# TBA820-Amplifier.net
KiCad netlist of a schematic drawn in EAGLE
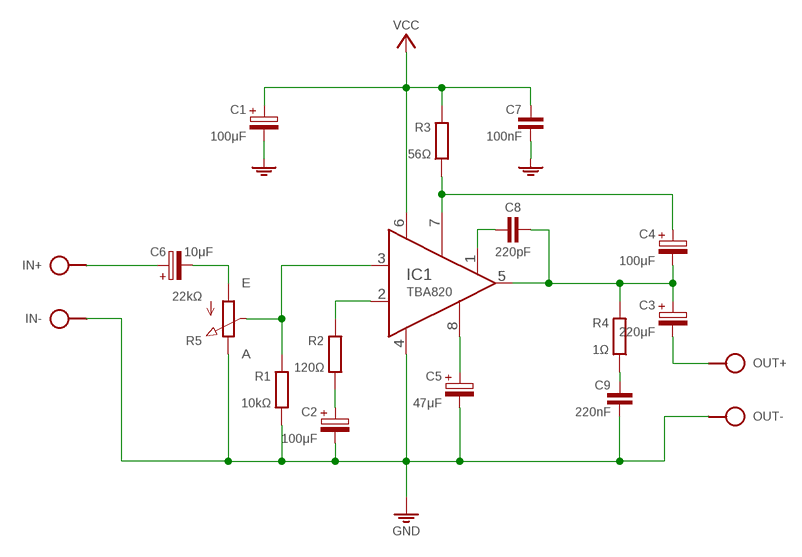
[diagram p0: schematic, sheet 1]

(export (version "E")
  (design (tool "Eeschema 10.0.6"))
  (components
    (comp (ref "C1")
      (value "100μF")
      (footprint "eagle-import:E2.5-4_V")
      (libsource (lib "eagle-import") (part "CPOLE2,5-4/V"))
    )
    (comp (ref "C2")
      (value "100μF")
      (footprint "eagle-import:E2.5-4_V")
      (libsource (lib "eagle-import") (part "CPOLE2,5-4/V"))
    )
    (comp (ref "C3")
      (value "220μF")
      (footprint "eagle-import:E2,5-5")
      (libsource (lib "eagle-import") (part "CPOLE2.5-5"))
    )
    (comp (ref "C4")
      (value "100μF")
      (footprint "eagle-import:E2.5-4_V")
      (libsource (lib "eagle-import") (part "CPOLE2,5-4/V"))
    )
    (comp (ref "C5")
      (value "47μF")
      (footprint "eagle-import:E2,5-3")
      (libsource (lib "eagle-import") (part "CPOLE2,5-3"))
    )
    (comp (ref "C6")
      (value "10μF")
      (footprint "eagle-import:E2,5-3")
      (libsource (lib "eagle-import") (part "CPOL-HE2,5-3"))
    )
    (comp (ref "C7")
      (value "100nF")
      (footprint "eagle-import:C025-024X044")
      (libsource (lib "eagle-import") (part "C025-024X044"))
    )
    (comp (ref "C8")
      (value "220pF")
      (footprint "eagle-import:C075-020X044")
      (libsource (lib "eagle-import") (part "C-H075-020X044"))
    )
    (comp (ref "C9")
      (value "220nF")
      (footprint "eagle-import:C075-020X044")
      (libsource (lib "eagle-import") (part "C075-020X044"))
    )
    (comp (ref "IC1")
      (value "TBA820")
      (footprint "eagle-import:DIL08")
      (libsource (lib "eagle-import") (part "TBA820"))
    )
    (comp (ref "IN")
      (value "SPAD+--+")
      (footprint "eagle-import:SPAD-+")
      (libsource (lib "eagle-import") (part "SPAD+--+"))
    )
    (comp (ref "OUT")
      (value "SPAD+-+-")
      (footprint "eagle-import:SPAD+-")
      (libsource (lib "eagle-import") (part "SPAD+-+-"))
    )
    (comp (ref "R1")
      (value "10kΩ")
      (footprint "eagle-import:0204_10-V")
      (libsource (lib "eagle-import") (part "R0204/10-V"))
    )
    (comp (ref "R2")
      (value "120Ω")
      (footprint "eagle-import:0202_2V")
      (libsource (lib "eagle-import") (part "R0202/2V"))
    )
    (comp (ref "R3")
      (value "56Ω")
      (footprint "eagle-import:0204_10-V")
      (libsource (lib "eagle-import") (part "R0204/10-V"))
    )
    (comp (ref "R4")
      (value "1Ω")
      (footprint "eagle-import:0204_10-V")
      (libsource (lib "eagle-import") (part "R0204/10-V"))
    )
    (comp (ref "R5")
      (value "22kΩ")
      (footprint "eagle-import:CONN-3P")
      (libsource (lib "eagle-import") (part "POT-3P"))
    )
    (comp (ref "S4")
      (value "VCC_GNDPWR-L")
      (footprint "eagle-import:PWR-L")
      (libsource (lib "eagle-import") (part "VCC_GNDPWR-L"))
    )
  )
  (nets
    (net (code "1") (name "GND") (class "Default")
      (node (ref "C1") (pin "-") (pinfunction "-_-") (pintype "passive"))
      (node (ref "C2") (pin "-") (pinfunction "-_-") (pintype "passive"))
      (node (ref "C5") (pin "-") (pinfunction "-_-") (pintype "passive"))
      (node (ref "C7") (pin "2") (pinfunction "2_2") (pintype "passive"))
      (node (ref "C9") (pin "2") (pinfunction "2_2") (pintype "passive"))
      (node (ref "IC1") (pin "4") (pinfunction "GND_4") (pintype "power_in"))
      (node (ref "IN") (pin "1") (pinfunction "P$1_1") (pintype "passive"))
      (node (ref "OUT") (pin "1") (pinfunction "P$1_1") (pintype "passive"))
      (node (ref "R1") (pin "2") (pinfunction "1_2") (pintype "passive"))
      (node (ref "R5") (pin "3") (pinfunction "E_3") (pintype "passive"))
      (node (ref "S4") (pin "1") (pinfunction "GND_1") (pintype "power_in"))
    )
    (net (code "2") (name "Net-(IC1-BOOT)") (class "Default")
      (node (ref "C4") (pin "+") (pinfunction "+_+") (pintype "passive"))
      (node (ref "IC1") (pin "7") (pinfunction "BOOT_7") (pintype "input"))
      (node (ref "R3") (pin "2") (pinfunction "1_2") (pintype "passive"))
    )
    (net (code "3") (name "Net-(IC1-FREQ)") (class "Default")
      (node (ref "C8") (pin "1") (pinfunction "1_1") (pintype "passive"))
      (node (ref "IC1") (pin "1") (pinfunction "FREQ_1") (pintype "input"))
    )
    (net (code "4") (name "Net-(IC1-GAIN)") (class "Default")
      (node (ref "IC1") (pin "2") (pinfunction "GAIN_2") (pintype "input"))
      (node (ref "R2") (pin "1") (pinfunction "2_1") (pintype "passive"))
    )
    (net (code "5") (name "Net-(IC1-INPUT)") (class "Default")
      (node (ref "IC1") (pin "3") (pinfunction "INPUT_3") (pintype "input"))
      (node (ref "R1") (pin "1") (pinfunction "2_1") (pintype "passive"))
      (node (ref "R5") (pin "2") (pinfunction "S_2") (pintype "passive"))
    )
    (net (code "6") (name "Net-(IC1-OUT)") (class "Default")
      (node (ref "C3") (pin "+") (pinfunction "+_+") (pintype "passive"))
      (node (ref "C4") (pin "-") (pinfunction "-_-") (pintype "passive"))
      (node (ref "C8") (pin "2") (pinfunction "2_2") (pintype "passive"))
      (node (ref "IC1") (pin "5") (pinfunction "OUT_5") (pintype "output"))
      (node (ref "R4") (pin "1") (pinfunction "2_1") (pintype "passive"))
    )
    (net (code "7") (name "Net-(IC1-RIPPLE)") (class "Default")
      (node (ref "C5") (pin "+") (pinfunction "+_+") (pintype "passive"))
      (node (ref "IC1") (pin "8") (pinfunction "RIPPLE_8") (pintype "input"))
    )
    (net (code "8") (name "Net-(IC1-VCC)") (class "Default")
      (node (ref "C1") (pin "+") (pinfunction "+_+") (pintype "passive"))
      (node (ref "C7") (pin "1") (pinfunction "1_1") (pintype "passive"))
      (node (ref "IC1") (pin "6") (pinfunction "VCC_6") (pintype "power_in"))
      (node (ref "R3") (pin "1") (pinfunction "2_1") (pintype "passive"))
      (node (ref "S4") (pin "2") (pinfunction "VCC_2") (pintype "power_in"))
    )
    (net (code "9") (name "Net-(INA-P$1)") (class "Default")
      (node (ref "C6") (pin "+") (pinfunction "+_+") (pintype "passive"))
      (node (ref "IN") (pin "2") (pinfunction "P$1_2") (pintype "passive"))
    )
    (net (code "10") (name "Net-(OUTA-P$1)") (class "Default")
      (node (ref "C3") (pin "-") (pinfunction "-_-") (pintype "passive"))
      (node (ref "OUT") (pin "2") (pinfunction "P$1_2") (pintype "passive"))
    )
    (net (code "11") (name "Net-(R2-1)") (class "Default")
      (node (ref "C2") (pin "+") (pinfunction "+_+") (pintype "passive"))
      (node (ref "R2") (pin "2") (pinfunction "1_2") (pintype "passive"))
    )
    (net (code "12") (name "Net-(R4-1)") (class "Default")
      (node (ref "C9") (pin "1") (pinfunction "1_1") (pintype "passive"))
      (node (ref "R4") (pin "2") (pinfunction "1_2") (pintype "passive"))
    )
    (net (code "13") (name "Net-(R5-A)") (class "Default")
      (node (ref "C6") (pin "-") (pinfunction "-_-") (pintype "passive"))
      (node (ref "R5") (pin "1") (pinfunction "A_1") (pintype "passive"))
    )
  )
)
